# DAB_FM_Radio.net
KiCad netlist of a schematic drawn in EAGLE
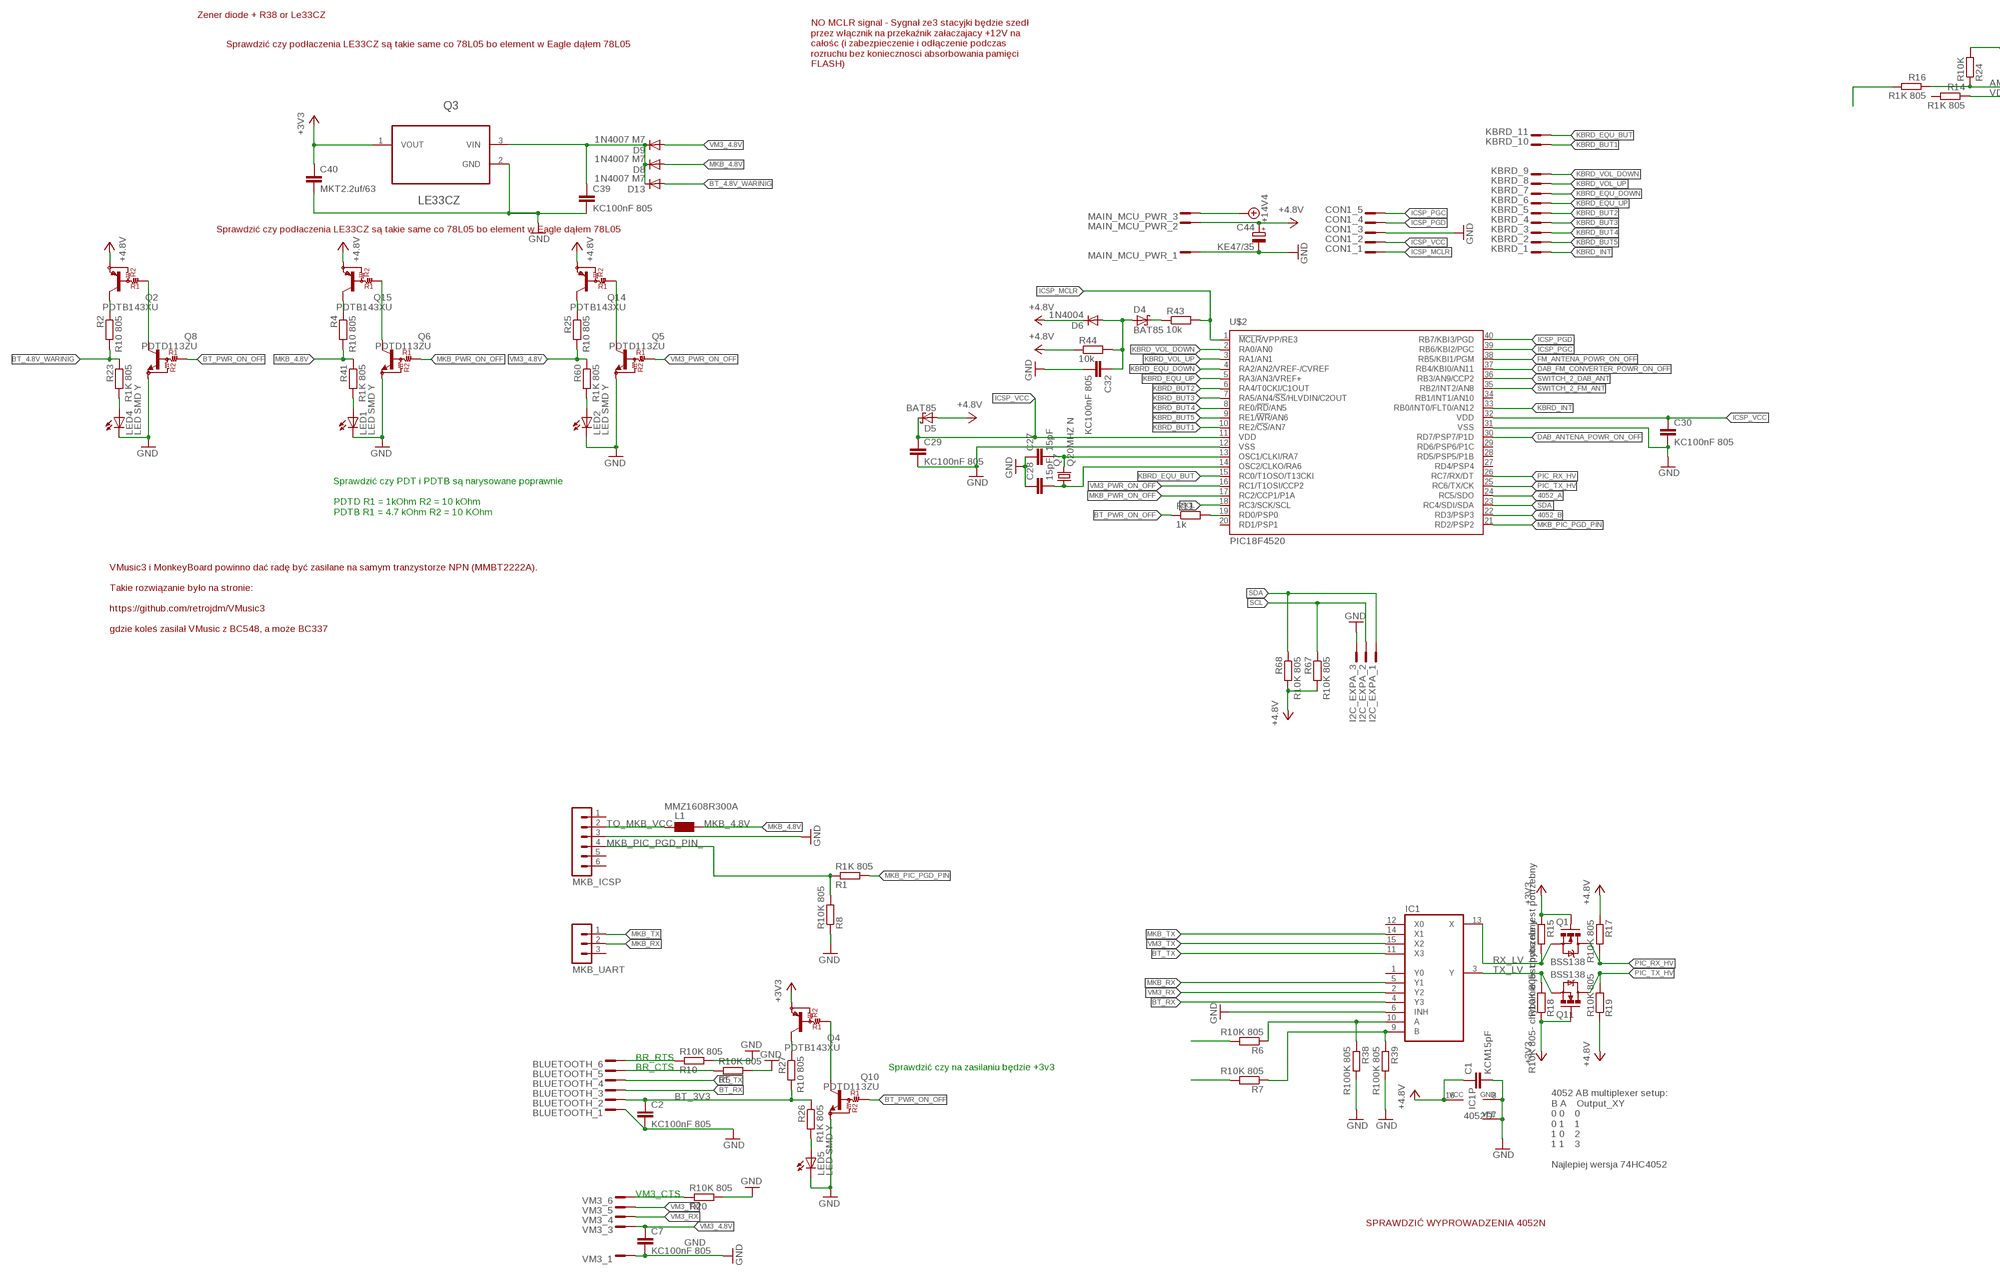
[diagram p0: schematic, sheet 1, part 1 of 2]
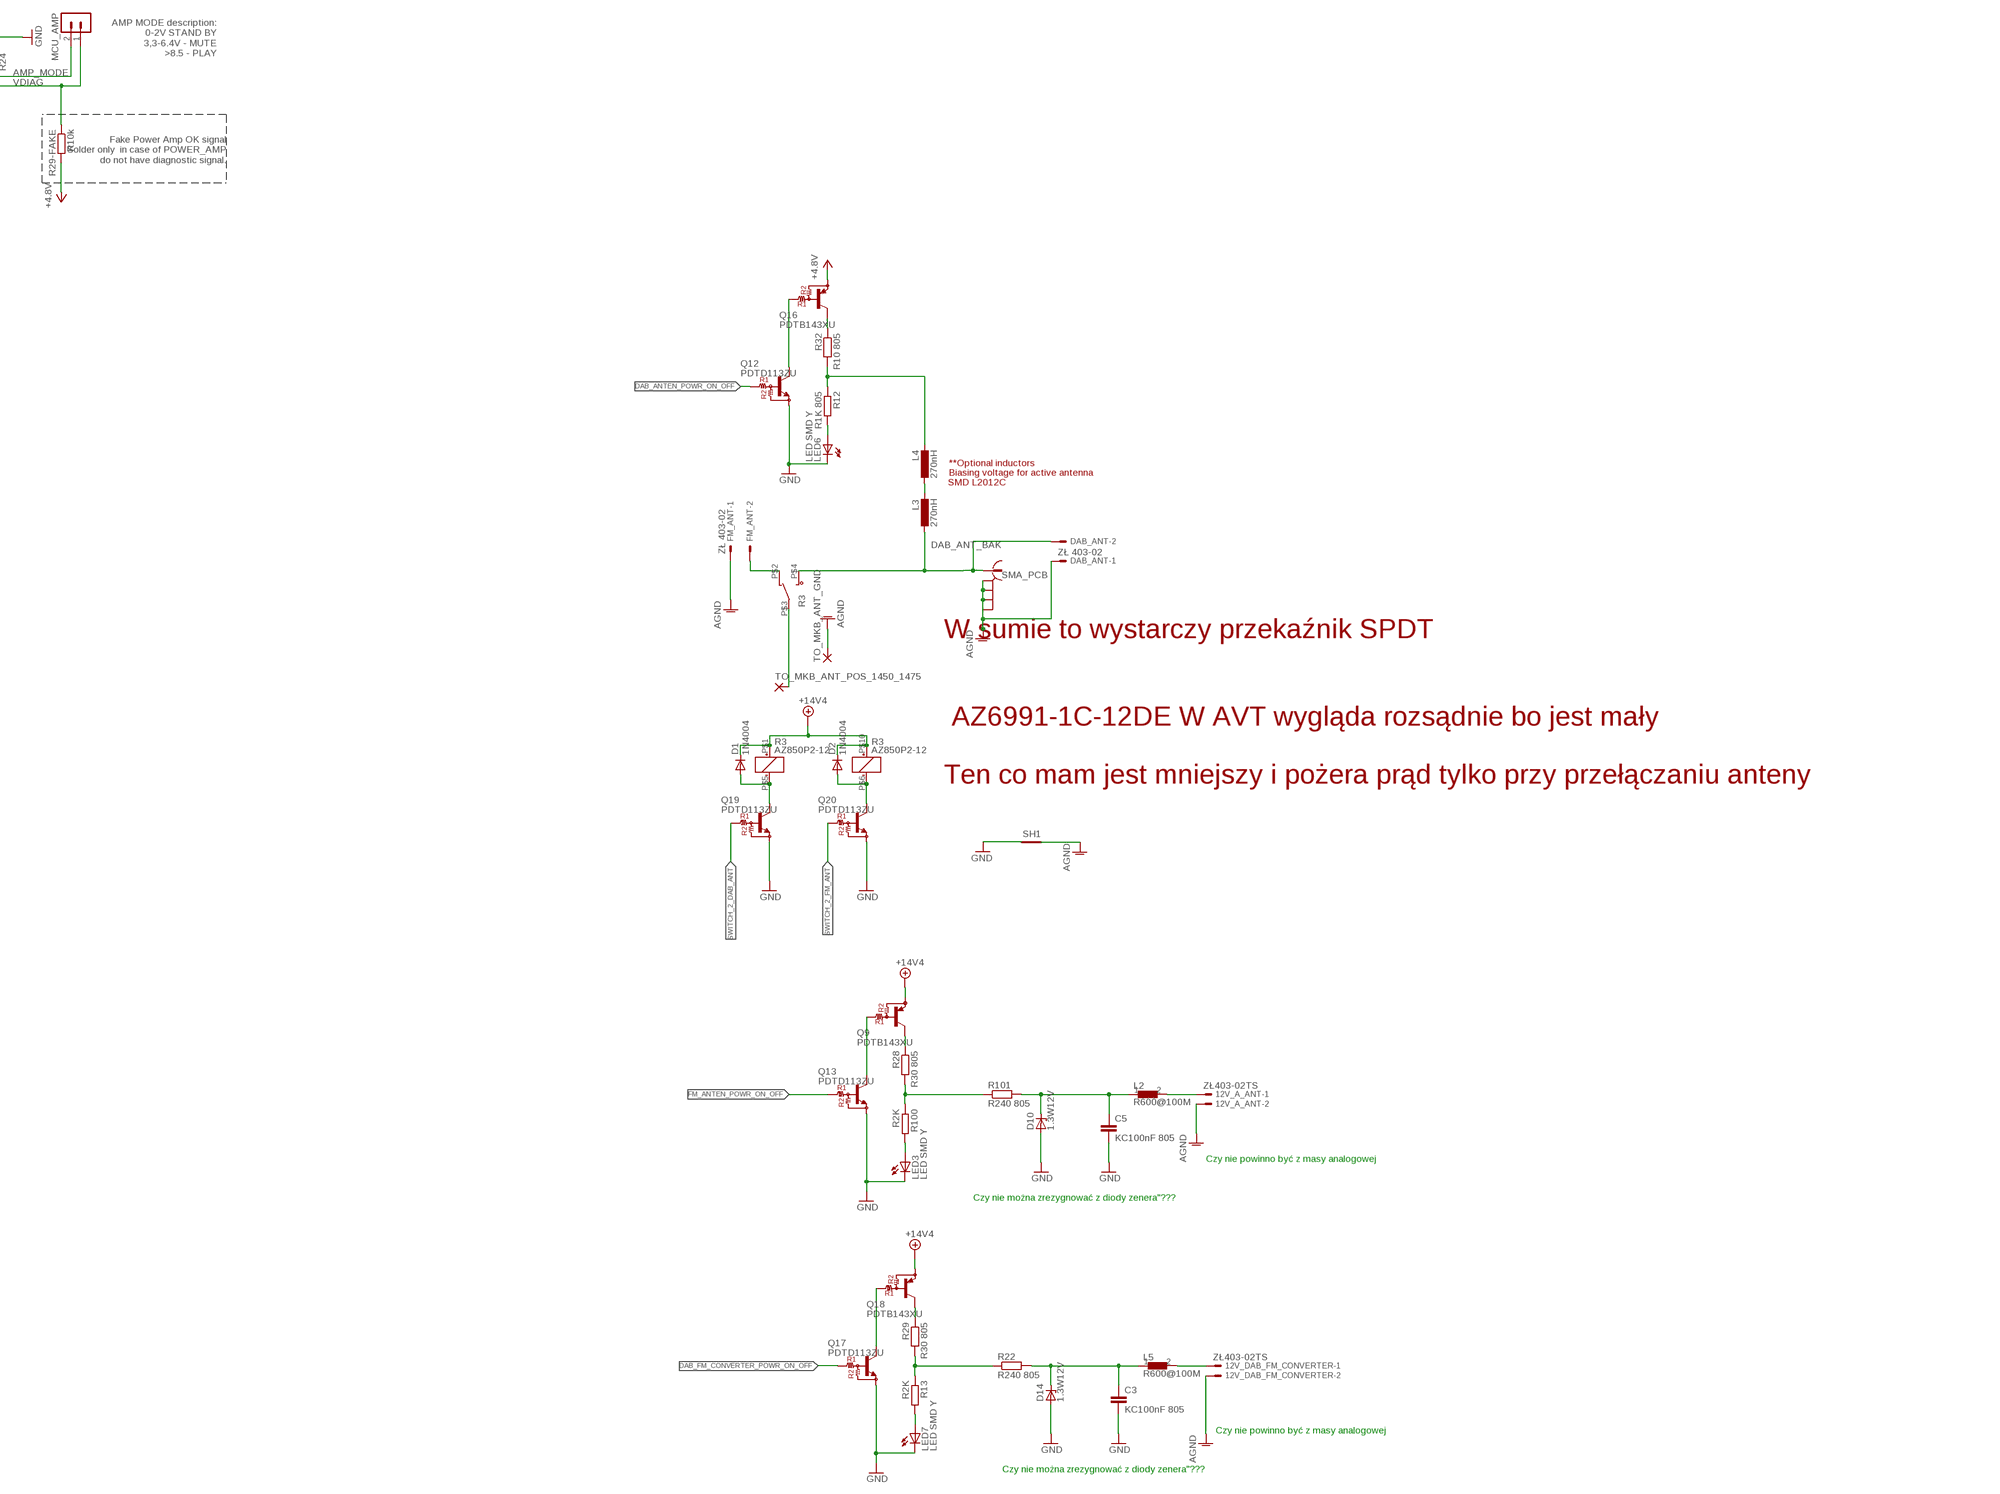
[diagram p1: schematic, sheet 1, part 2 of 2]

(export (version "E")
  (design (tool "Eeschema 10.0.6"))
  (components
    (comp (ref "12V_A_ANT")
      (value "ZŁ403-02TS")
      (footprint "eagle-import:22-23-2021")
      (fields (field (name "MF") "MOLEX") (field (name "MPN") "22-23-2021"))
      (libsource (lib "eagle-import") (part "22-23-2021"))
    )
    (comp (ref "12V_DAB_FM_CONVERTER")
      (value "ZŁ403-02TS")
      (footprint "eagle-import:22-23-2021")
      (fields (field (name "MF") "MOLEX") (field (name "MPN") "22-23-2021"))
      (libsource (lib "eagle-import") (part "22-23-2021"))
    )
    (comp (ref "BLUETOOTH")
      (value "JST_6_PIN_B6B-PH-KS")
      (footprint "eagle-import:B6B-PH-KS")
      (libsource (lib "eagle-import") (part "JST_6_PIN_B6B-PH-KS"))
    )
    (comp (ref "C1")
      (value "KCM15pF")
      (footprint "eagle-import:C0805")
      (libsource (lib "eagle-import") (part "C-EUC0805"))
    )
    (comp (ref "C2")
      (value "KC100nF 805")
      (footprint "eagle-import:C0805")
      (libsource (lib "eagle-import") (part "C-EUC0805"))
    )
    (comp (ref "C3")
      (value "KC100nF 805")
      (footprint "eagle-import:C0805")
      (libsource (lib "eagle-import") (part "C-EUC0805"))
    )
    (comp (ref "C5")
      (value "KC100nF 805")
      (footprint "eagle-import:C0805")
      (libsource (lib "eagle-import") (part "C-EUC0805"))
    )
    (comp (ref "C7")
      (value "KC100nF 805")
      (footprint "eagle-import:C0805")
      (libsource (lib "eagle-import") (part "C-EUC0805"))
    )
    (comp (ref "C27")
      (value "15pF")
      (footprint "eagle-import:C0805")
      (libsource (lib "eagle-import") (part "C-EUC0805"))
    )
    (comp (ref "C28")
      (value "15pF")
      (footprint "eagle-import:C0805")
      (libsource (lib "eagle-import") (part "C-EUC0805"))
    )
    (comp (ref "C29")
      (value "KC100nF 805")
      (footprint "eagle-import:C0805")
      (libsource (lib "eagle-import") (part "C-EUC0805"))
    )
    (comp (ref "C30")
      (value "KC100nF 805")
      (footprint "eagle-import:C0805")
      (libsource (lib "eagle-import") (part "C-EUC0805"))
    )
    (comp (ref "C32")
      (value "KC100nF 805")
      (footprint "eagle-import:C0805")
      (libsource (lib "eagle-import") (part "C-EUC0805"))
    )
    (comp (ref "C39")
      (value "KC100nF 805")
      (footprint "eagle-import:C0805")
      (libsource (lib "eagle-import") (part "C-EUC0805"))
    )
    (comp (ref "C40")
      (value "MKT2.2uf/63")
      (footprint "eagle-import:C025-030X050")
      (libsource (lib "eagle-import") (part "C-EU025-030X050"))
    )
    (comp (ref "C44")
      (value "KE47/35")
      (footprint "eagle-import:TT2D6")
      (libsource (lib "eagle-import") (part "CPOL-EUTT2D6"))
    )
    (comp (ref "CON1")
      (value "JST_5_PIN_B5B-PH-KS")
      (footprint "eagle-import:B5B-PH-KS")
      (libsource (lib "eagle-import") (part "JST_5_PIN_B5B-PH-KS"))
    )
    (comp (ref "D1")
      (value "1N4004")
      (footprint "eagle-import:DO41-7.6")
      (libsource (lib "eagle-import") (part "1N4004DO41-7.6"))
    )
    (comp (ref "D2")
      (value "1N4004")
      (footprint "eagle-import:DO41-7.6")
      (libsource (lib "eagle-import") (part "1N4004DO41-7.6"))
    )
    (comp (ref "D4")
      (value "BAT85")
      (footprint "eagle-import:DO34-V")
      (libsource (lib "eagle-import") (part "BAT85DO34-V"))
    )
    (comp (ref "D5")
      (value "BAT85")
      (footprint "eagle-import:DO34-5")
      (libsource (lib "eagle-import") (part "BAT85DO34-5"))
    )
    (comp (ref "D6")
      (value "1N4004")
      (footprint "eagle-import:DO41-V")
      (libsource (lib "eagle-import") (part "1N4004DO41-V"))
    )
    (comp (ref "D8")
      (value "1N4007 M7")
      (footprint "eagle-import:DO41-V")
      (libsource (lib "eagle-import") (part "1N4004DO41-V"))
    )
    (comp (ref "D9")
      (value "1N4007 M7")
      (footprint "eagle-import:DO41-V")
      (libsource (lib "eagle-import") (part "1N4004DO41-V"))
    )
    (comp (ref "D10")
      (value "1.3W12V")
      (footprint "eagle-import:ZDIO-2.5")
      (libsource (lib "eagle-import") (part "ZENER-DIODEZD-2.5"))
    )
    (comp (ref "D13")
      (value "1N4007 M7")
      (footprint "eagle-import:DO41-V")
      (libsource (lib "eagle-import") (part "1N4004DO41-V"))
    )
    (comp (ref "D14")
      (value "1.3W12V")
      (footprint "eagle-import:ZDIO-2.5")
      (libsource (lib "eagle-import") (part "ZENER-DIODEZD-2.5"))
    )
    (comp (ref "DAB_ANT")
      (value "ZŁ 403-02")
      (footprint "eagle-import:6410-02")
      (fields (field (name "OC_FARNELL") "unknown") (field (name "OC_NEWARK") "unknown"))
      (libsource (lib "eagle-import") (part "22-?-0227-2021"))
    )
    (comp (ref "DAB_ANT_BAK")
      (value "SMA_PCB")
      (footprint "eagle-import:SMA_PCB")
      (libsource (lib "eagle-import") (part "SMA_PCB"))
    )
    (comp (ref "FM_ANT")
      (value "ZŁ 403-02")
      (footprint "eagle-import:6410-02")
      (libsource (lib "eagle-import") (part "22-?-0227-2021"))
    )
    (comp (ref "I2C_EXPA")
      (value "JST_3_PIN_B3B-PH-KS")
      (footprint "eagle-import:B3B-PH-KS")
      (libsource (lib "eagle-import") (part "JST_3_PIN_B3B-PH-KS"))
    )
    (comp (ref "IC1")
      (value "4052D")
      (footprint "eagle-import:SO16")
      (libsource (lib "eagle-import") (part "4052D"))
    )
    (comp (ref "KBRD")
      (value "JST_11_PIN_B11B-PH-KS")
      (footprint "eagle-import:B11B-PH-KS")
      (libsource (lib "eagle-import") (part "JST_11_PIN_B11B-PH-KS"))
    )
    (comp (ref "L1")
      (value "MMZ1608R300A")
      (footprint "eagle-import:0603")
      (libsource (lib "eagle-import") (part "WE-CBF_0603"))
    )
    (comp (ref "L2")
      (value "R600@100M")
      (footprint "eagle-import:R0805")
      (libsource (lib "eagle-import") (part "FERRITR0805"))
    )
    (comp (ref "L3")
      (value "270nH")
      (footprint "eagle-import:L2012C")
      (libsource (lib "eagle-import") (part "L-EUL2012C"))
    )
    (comp (ref "L4")
      (value "270nH")
      (footprint "eagle-import:L2012C")
      (libsource (lib "eagle-import") (part "L-EUL2012C"))
    )
    (comp (ref "L5")
      (value "R600@100M")
      (footprint "eagle-import:R0805")
      (libsource (lib "eagle-import") (part "FERRITR0805"))
    )
    (comp (ref "LED1")
      (value "LED SMD Y")
      (footprint "eagle-import:CHIP-LED0805")
      (libsource (lib "eagle-import") (part "LEDCHIP-LED0805"))
    )
    (comp (ref "LED2")
      (value "LED SMD Y")
      (footprint "eagle-import:CHIP-LED0805")
      (libsource (lib "eagle-import") (part "LEDCHIP-LED0805"))
    )
    (comp (ref "LED3")
      (value "LED SMD Y")
      (footprint "eagle-import:SMARTLED-TTW")
      (libsource (lib "eagle-import") (part "LED"))
    )
    (comp (ref "LED4")
      (value "LED SMD Y")
      (footprint "eagle-import:CHIP-LED0805")
      (libsource (lib "eagle-import") (part "LEDCHIP-LED0805"))
    )
    (comp (ref "LED5")
      (value "LED SMD Y")
      (footprint "eagle-import:CHIP-LED0805")
      (libsource (lib "eagle-import") (part "LEDCHIP-LED0805"))
    )
    (comp (ref "LED6")
      (value "LED SMD Y")
      (footprint "eagle-import:SMARTLED-TTW")
      (libsource (lib "eagle-import") (part "LED"))
    )
    (comp (ref "LED7")
      (value "LED SMD Y")
      (footprint "eagle-import:SMARTLED-TTW")
      (libsource (lib "eagle-import") (part "LED"))
    )
    (comp (ref "MAIN_MCU_PWR")
      (value "JST_3_PIN_B3B-XH-A")
      (footprint "eagle-import:B3B-XH-A")
      (libsource (lib "eagle-import") (part "JST_3_PIN_B3B-XH-A"))
    )
    (comp (ref "MCU_AMP")
      (value "MA02-1")
      (footprint "eagle-import:MA02-1")
      (libsource (lib "eagle-import") (part "MA02-1"))
    )
    (comp (ref "MKB_ICSP")
      (value "MA06-1")
      (footprint "eagle-import:MA06-1")
      (libsource (lib "eagle-import") (part "MA06-1"))
    )
    (comp (ref "MKB_UART")
      (value "MA03-1")
      (footprint "eagle-import:MA03-1")
      (libsource (lib "eagle-import") (part "MA03-1"))
    )
    (comp (ref "Q1")
      (value "BSS138")
      (footprint "eagle-import:SOT23-3")
      (libsource (lib "eagle-import") (part "MOSFET-NCHANNELSMD"))
    )
    (comp (ref "Q2")
      (value "PDTB143XU")
      (footprint "eagle-import:SOT-23")
      (fields (field (name "R1") "4.7 kOhm") (field (name "R2") "10 kOhm"))
      (libsource (lib "eagle-import") (part "PDTB143XU"))
    )
    (comp (ref "Q3")
      (value "LE33CZ")
      (footprint "eagle-import:TO127P254X749-3")
      (libsource (lib "eagle-import") (part "LE33CZ"))
    )
    (comp (ref "Q4")
      (value "PDTB143XU")
      (footprint "eagle-import:SOT-23")
      (fields (field (name "R1") "4.7 kOhm") (field (name "R2") "10 kOhm"))
      (libsource (lib "eagle-import") (part "PDTB143XU"))
    )
    (comp (ref "Q5")
      (value "PDTD113ZU")
      (footprint "eagle-import:SOT-23")
      (libsource (lib "eagle-import") (part "PDTD113ZU"))
    )
    (comp (ref "Q6")
      (value "PDTD113ZU")
      (footprint "eagle-import:SOT-23")
      (fields (field (name "R1") "1 kOhm") (field (name "R2") "10 kOhm"))
      (libsource (lib "eagle-import") (part "PDTD113ZU"))
    )
    (comp (ref "Q7")
      (value "Q20MHZ N")
      (footprint "eagle-import:HC49_S")
      (libsource (lib "eagle-import") (part "CRYSTALHC49S"))
    )
    (comp (ref "Q8")
      (value "PDTD113ZU")
      (footprint "eagle-import:SOT-23")
      (fields (field (name "R1") "1 kOhm") (field (name "R2") "10 kOhm"))
      (libsource (lib "eagle-import") (part "PDTD113ZU"))
    )
    (comp (ref "Q9")
      (value "PDTB143XU")
      (footprint "eagle-import:SOT-23")
      (fields (field (name "R1") "4.7 kOhm") (field (name "R2") "10 kOhm"))
      (libsource (lib "eagle-import") (part "PDTB143XU"))
    )
    (comp (ref "Q10")
      (value "PDTD113ZU")
      (footprint "eagle-import:SOT-23")
      (fields (field (name "R1") "1 kOhm") (field (name "R2") "10 kOhm"))
      (libsource (lib "eagle-import") (part "PDTD113ZU"))
    )
    (comp (ref "Q11")
      (value "BSS138")
      (footprint "eagle-import:SOT23-3")
      (libsource (lib "eagle-import") (part "MOSFET-NCHANNELSMD"))
    )
    (comp (ref "Q12")
      (value "PDTD113ZU")
      (footprint "eagle-import:SOT-23")
      (fields (field (name "R1") "1 kOhm") (field (name "R2") "10 kOhm"))
      (libsource (lib "eagle-import") (part "PDTD113ZU"))
    )
    (comp (ref "Q13")
      (value "PDTD113ZU")
      (footprint "eagle-import:SOT-23")
      (fields (field (name "R1") "1 kOhm") (field (name "R2") "10 kOhm"))
      (libsource (lib "eagle-import") (part "PDTD113ZU"))
    )
    (comp (ref "Q14")
      (value "PDTB143XU")
      (footprint "eagle-import:SOT-23")
      (libsource (lib "eagle-import") (part "PDTB143XU"))
    )
    (comp (ref "Q15")
      (value "PDTB143XU")
      (footprint "eagle-import:SOT-23")
      (fields (field (name "R1") "4.7 kOhm") (field (name "R2") "10 kOhm"))
      (libsource (lib "eagle-import") (part "PDTB143XU"))
    )
    (comp (ref "Q16")
      (value "PDTB143XU")
      (footprint "eagle-import:SOT-23")
      (fields (field (name "R1") "4.7 kOhm") (field (name "R2") "10 kOhm"))
      (libsource (lib "eagle-import") (part "PDTB143XU"))
    )
    (comp (ref "Q17")
      (value "PDTD113ZU")
      (footprint "eagle-import:SOT-23")
      (fields (field (name "R1") "1 kOhm") (field (name "R2") "10 kOhm"))
      (libsource (lib "eagle-import") (part "PDTD113ZU"))
    )
    (comp (ref "Q18")
      (value "PDTB143XU")
      (footprint "eagle-import:SOT-23")
      (fields (field (name "R1") "4.7 kOhm") (field (name "R2") "10 kOhm"))
      (libsource (lib "eagle-import") (part "PDTB143XU"))
    )
    (comp (ref "Q19")
      (value "PDTD113ZU")
      (footprint "eagle-import:SOT-23")
      (fields (field (name "R1") "1 kOhm") (field (name "R2") "10 kOhm"))
      (libsource (lib "eagle-import") (part "PDTD113ZU"))
    )
    (comp (ref "Q20")
      (value "PDTD113ZU")
      (footprint "eagle-import:SOT-23")
      (fields (field (name "R1") "1 kOhm") (field (name "R2") "10 kOhm"))
      (libsource (lib "eagle-import") (part "PDTD113ZU"))
    )
    (comp (ref "R1")
      (value "R1K 805")
      (footprint "eagle-import:R0805")
      (libsource (lib "eagle-import") (part "R-EU_R0805"))
    )
    (comp (ref "R2")
      (value "R10 805")
      (footprint "eagle-import:R0805")
      (libsource (lib "eagle-import") (part "R-EU_R0805"))
    )
    (comp (ref "R3")
      (value "AZ850P2-12")
      (footprint "eagle-import:AZ850-2C")
      (libsource (lib "eagle-import") (part "AZ850P2-12"))
    )
    (comp (ref "R4")
      (value "R10 805")
      (footprint "eagle-import:R0805")
      (libsource (lib "eagle-import") (part "R-EU_R0805"))
    )
    (comp (ref "R5")
      (value "R10K 805")
      (footprint "eagle-import:R0805")
      (libsource (lib "eagle-import") (part "R-EU_R0805"))
    )
    (comp (ref "R6")
      (value "R10K 805")
      (footprint "eagle-import:R0805")
      (libsource (lib "eagle-import") (part "R-EU_R0805"))
    )
    (comp (ref "R7")
      (value "R10K 805")
      (footprint "eagle-import:R0805")
      (libsource (lib "eagle-import") (part "R-EU_R0805"))
    )
    (comp (ref "R8")
      (value "R10K 805")
      (footprint "eagle-import:R0805")
      (libsource (lib "eagle-import") (part "R-EU_R0805"))
    )
    (comp (ref "R10")
      (value "R10K 805")
      (footprint "eagle-import:R0805")
      (libsource (lib "eagle-import") (part "R-EU_R0805"))
    )
    (comp (ref "R11")
      (value "1k")
      (footprint "eagle-import:R0805")
      (libsource (lib "eagle-import") (part "R-EU_R0805"))
    )
    (comp (ref "R12")
      (value "R1K 805")
      (footprint "eagle-import:R0805")
      (libsource (lib "eagle-import") (part "R-EU_R0805"))
    )
    (comp (ref "R13")
      (value "R2K")
      (footprint "eagle-import:R0805")
      (libsource (lib "eagle-import") (part "R-EU_R0805"))
    )
    (comp (ref "R14")
      (value "R1K 805")
      (footprint "eagle-import:R0805")
      (libsource (lib "eagle-import") (part "R-EU_R0805"))
    )
    (comp (ref "R15")
      (value "R10K 805- chyba nie jest potrzebny")
      (footprint "eagle-import:R0805")
      (libsource (lib "eagle-import") (part "R-EU_R0805"))
    )
    (comp (ref "R16")
      (value "R1K 805")
      (footprint "eagle-import:R0805")
      (libsource (lib "eagle-import") (part "R-EU_R0805"))
    )
    (comp (ref "R17")
      (value "R10K 805")
      (footprint "eagle-import:R0805")
      (libsource (lib "eagle-import") (part "R-EU_R0805"))
    )
    (comp (ref "R18")
      (value "R10K 805- chyba nie jest potrzebny")
      (footprint "eagle-import:R0805")
      (libsource (lib "eagle-import") (part "R-EU_R0805"))
    )
    (comp (ref "R19")
      (value "R10K 805")
      (footprint "eagle-import:R0805")
      (libsource (lib "eagle-import") (part "R-EU_R0805"))
    )
    (comp (ref "R20")
      (value "R10K 805")
      (footprint "eagle-import:R0805")
      (libsource (lib "eagle-import") (part "R-EU_R0805"))
    )
    (comp (ref "R22")
      (value "R240 805")
      (footprint "eagle-import:M0805")
      (libsource (lib "eagle-import") (part "R-EU_M0805"))
    )
    (comp (ref "R23")
      (value "R1K 805")
      (footprint "eagle-import:R0805")
      (libsource (lib "eagle-import") (part "R-EU_R0805"))
    )
    (comp (ref "R24")
      (value "R10K")
      (footprint "eagle-import:R0805")
      (libsource (lib "eagle-import") (part "R-EU_R0805"))
    )
    (comp (ref "R25")
      (value "R10 805")
      (footprint "eagle-import:R0805")
      (libsource (lib "eagle-import") (part "R-EU_R0805"))
    )
    (comp (ref "R26")
      (value "R1K 805")
      (footprint "eagle-import:R0805")
      (libsource (lib "eagle-import") (part "R-EU_R0805"))
    )
    (comp (ref "R27")
      (value "R10 805")
      (footprint "eagle-import:R0805")
      (libsource (lib "eagle-import") (part "R-EU_R0805"))
    )
    (comp (ref "R28")
      (value "R30 805")
      (footprint "eagle-import:R0805")
      (libsource (lib "eagle-import") (part "R-EU_R0805"))
    )
    (comp (ref "R29")
      (value "R30 805")
      (footprint "eagle-import:R0805")
      (libsource (lib "eagle-import") (part "R-EU_R0805"))
    )
    (comp (ref "R29-FAKE")
      (value "R10k")
      (footprint "eagle-import:0204_7")
      (libsource (lib "eagle-import") (part "R-EU_0204/7"))
    )
    (comp (ref "R32")
      (value "R10 805")
      (footprint "eagle-import:R0805")
      (libsource (lib "eagle-import") (part "R-EU_R0805"))
    )
    (comp (ref "R38")
      (value "R100K 805")
      (footprint "eagle-import:M0805")
      (libsource (lib "eagle-import") (part "R-EU_M0805"))
    )
    (comp (ref "R39")
      (value "R100K 805")
      (footprint "eagle-import:M0805")
      (libsource (lib "eagle-import") (part "R-EU_M0805"))
    )
    (comp (ref "R41")
      (value "R1K 805")
      (footprint "eagle-import:R0805")
      (libsource (lib "eagle-import") (part "R-EU_R0805"))
    )
    (comp (ref "R43")
      (value "10k")
      (footprint "eagle-import:R0805")
      (libsource (lib "eagle-import") (part "R-EU_R0805"))
    )
    (comp (ref "R44")
      (value "10k")
      (footprint "eagle-import:M0805")
      (libsource (lib "eagle-import") (part "R-EU_M0805"))
    )
    (comp (ref "R60")
      (value "R1K 805")
      (footprint "eagle-import:R0805")
      (libsource (lib "eagle-import") (part "R-EU_R0805"))
    )
    (comp (ref "R67")
      (value "R10K 805")
      (footprint "eagle-import:R0805")
      (libsource (lib "eagle-import") (part "R-EU_R0805"))
    )
    (comp (ref "R68")
      (value "R10K 805")
      (footprint "eagle-import:R0805")
      (libsource (lib "eagle-import") (part "R-EU_R0805"))
    )
    (comp (ref "R100")
      (value "R2K")
      (footprint "eagle-import:R0805")
      (libsource (lib "eagle-import") (part "R-EU_R0805"))
    )
    (comp (ref "R101")
      (value "R240 805")
      (footprint "eagle-import:M0805")
      (libsource (lib "eagle-import") (part "R-EU_M0805"))
    )
    (comp (ref "SH1")
      (value "SHORT-HT5")
      (footprint "eagle-import:SHORT_TOP-50")
      (libsource (lib "eagle-import") (part "SHORT-HT5"))
    )
    (comp (ref "TO_MKB_ANT_GND")
      (value "2,54/0,8")
      (footprint "eagle-import:2,54_0,8")
      (libsource (lib "eagle-import") (part "2,54/0,8"))
    )
    (comp (ref "TO_MKB_ANT_POS_1450_1475")
      (value "2,54/0,8")
      (footprint "eagle-import:2,54_0,8")
      (libsource (lib "eagle-import") (part "2,54/0,8"))
    )
    (comp (ref "U$2")
      (value "PIC18F4520")
      (footprint "eagle-import:DIL40")
      (libsource (lib "eagle-import") (part "PIC18F4205"))
    )
    (comp (ref "VM3")
      (value "JST_6_PIN_B6B-PH-KS")
      (footprint "eagle-import:B6B-PH-KS")
      (libsource (lib "eagle-import") (part "JST_6_PIN_B6B-PH-KS"))
    )
  )
  (nets
    (net (code "1") (name "+3V3") (class "Default")
      (node (ref "C40") (pin "1") (pinfunction "1_1") (pintype "passive"))
      (node (ref "Q1") (pin "1") (pinfunction "G_1") (pintype "passive"))
      (node (ref "Q11") (pin "1") (pinfunction "G_1") (pintype "passive"))
      (node (ref "Q3") (pin "1") (pinfunction "VOUT_1") (pintype "output"))
      (node (ref "Q4") (pin "2") (pinfunction "E_2") (pintype "passive"))
      (node (ref "R15") (pin "1") (pinfunction "1_1") (pintype "passive"))
      (node (ref "R18") (pin "1") (pinfunction "1_1") (pintype "passive"))
    )
    (net (code "2") (name "+4.8V") (class "Default")
      (node (ref "C1") (pin "1") (pinfunction "1_1") (pintype "passive"))
      (node (ref "C44") (pin "+") (pinfunction "+_+") (pintype "passive"))
      (node (ref "D5") (pin "A") (pinfunction "A_A") (pintype "passive"))
      (node (ref "D6") (pin "C") (pinfunction "C_C") (pintype "passive"))
      (node (ref "IC1") (pin "16") (pinfunction "VCC_16") (pintype "power_in"))
      (node (ref "MAIN_MCU_PWR") (pin "P$2") (pinfunction "P$1_P$2") (pintype "bidirectional"))
      (node (ref "Q14") (pin "2") (pinfunction "E_2") (pintype "passive"))
      (node (ref "Q15") (pin "2") (pinfunction "E_2") (pintype "passive"))
      (node (ref "Q16") (pin "2") (pinfunction "E_2") (pintype "passive"))
      (node (ref "Q2") (pin "2") (pinfunction "E_2") (pintype "passive"))
      (node (ref "R17") (pin "1") (pinfunction "1_1") (pintype "passive"))
      (node (ref "R19") (pin "1") (pinfunction "1_1") (pintype "passive"))
      (node (ref "R29-FAKE") (pin "2") (pinfunction "2_2") (pintype "passive"))
      (node (ref "R44") (pin "1") (pinfunction "1_1") (pintype "passive"))
      (node (ref "R67") (pin "2") (pinfunction "2_2") (pintype "passive"))
      (node (ref "R68") (pin "2") (pinfunction "2_2") (pintype "passive"))
    )
    (net (code "3") (name "+14V4") (class "Default")
      (node (ref "D1") (pin "C") (pinfunction "C_C") (pintype "passive"))
      (node (ref "D2") (pin "C") (pinfunction "C_C") (pintype "passive"))
      (node (ref "MAIN_MCU_PWR") (pin "P$3") (pinfunction "P$1_P$3") (pintype "bidirectional"))
      (node (ref "Q18") (pin "2") (pinfunction "E_2") (pintype "passive"))
      (node (ref "Q9") (pin "2") (pinfunction "E_2") (pintype "passive"))
      (node (ref "R3") (pin "P$1") (pinfunction "+_P$1") (pintype "passive"))
      (node (ref "R3") (pin "P$10") (pinfunction "+_P$10") (pintype "passive"))
    )
    (net (code "4") (name "/AMP_MODE") (class "Default")
      (node (ref "MCU_AMP") (pin "2") (pinfunction "2_2") (pintype "passive"))
      (node (ref "R16") (pin "1") (pinfunction "1_1") (pintype "passive"))
      (node (ref "R24") (pin "1") (pinfunction "1_1") (pintype "passive"))
    )
    (net (code "5") (name "/BT_3V3") (class "Default")
      (node (ref "BLUETOOTH") (pin "P$2") (pinfunction "P$1_P$2") (pintype "bidirectional"))
      (node (ref "C2") (pin "1") (pinfunction "1_1") (pintype "passive"))
      (node (ref "R26") (pin "1") (pinfunction "1_1") (pintype "passive"))
      (node (ref "R27") (pin "2") (pinfunction "2_2") (pintype "passive"))
    )
    (net (code "6") (name "/MKB_PIC_PGD_PIN_") (class "Default")
      (node (ref "MKB_ICSP") (pin "4") (pinfunction "4_4") (pintype "passive"))
      (node (ref "R1") (pin "1") (pinfunction "1_1") (pintype "passive"))
      (node (ref "R8") (pin "2") (pinfunction "2_2") (pintype "passive"))
    )
    (net (code "7") (name "/RX_LV") (class "Default")
      (node (ref "IC1") (pin "13") (pinfunction "X_13") (pintype "bidirectional"))
      (node (ref "Q1") (pin "2") (pinfunction "S_2") (pintype "passive"))
      (node (ref "R15") (pin "2") (pinfunction "2_2") (pintype "passive"))
    )
    (net (code "8") (name "/TO_MKB_VCC") (class "Default")
      (node (ref "L1") (pin "1") (pinfunction "1_1") (pintype "passive"))
      (node (ref "MKB_ICSP") (pin "2") (pinfunction "2_2") (pintype "passive"))
    )
    (net (code "9") (name "/TX_LV") (class "Default")
      (node (ref "IC1") (pin "3") (pinfunction "Y_3") (pintype "bidirectional"))
      (node (ref "Q11") (pin "2") (pinfunction "S_2") (pintype "passive"))
      (node (ref "R18") (pin "2") (pinfunction "2_2") (pintype "passive"))
    )
    (net (code "10") (name "/VDIAG") (class "Default")
      (node (ref "MCU_AMP") (pin "1") (pinfunction "1_1") (pintype "passive"))
      (node (ref "R14") (pin "1") (pinfunction "1_1") (pintype "passive"))
      (node (ref "R29-FAKE") (pin "1") (pinfunction "1_1") (pintype "passive"))
    )
    (net (code "11") (name "4052_A") (class "Default")
      (node (ref "R6") (pin "2") (pinfunction "2_2") (pintype "passive"))
      (node (ref "U$2") (pin "24") (pinfunction "RC5/SDO_24") (pintype "bidirectional"))
    )
    (net (code "12") (name "4052_B") (class "Default")
      (node (ref "R7") (pin "2") (pinfunction "2_2") (pintype "passive"))
      (node (ref "U$2") (pin "22") (pinfunction "RD3/PSP3_22") (pintype "bidirectional"))
    )
    (net (code "13") (name "AGND") (class "Default")
      (node (ref "12V_A_ANT") (pin "2") (pinfunction "S_2") (pintype "passive"))
      (node (ref "12V_DAB_FM_CONVERTER") (pin "2") (pinfunction "S_2") (pintype "passive"))
      (node (ref "DAB_ANT") (pin "1") (pinfunction "S_1") (pintype "passive"))
      (node (ref "DAB_ANT_BAK") (pin "GND@1") (pinfunction "GND_GND@1") (pintype "power_in"))
      (node (ref "DAB_ANT_BAK") (pin "GND@2") (pinfunction "GND_GND@2") (pintype "power_in"))
      (node (ref "DAB_ANT_BAK") (pin "GND@3") (pinfunction "GND_GND@3") (pintype "power_in"))
      (node (ref "DAB_ANT_BAK") (pin "GND@4") (pinfunction "GND_GND@4") (pintype "power_in"))
      (node (ref "FM_ANT") (pin "1") (pinfunction "S_1") (pintype "passive"))
      (node (ref "SH1") (pin "2") (pinfunction "P$2_2") (pintype "bidirectional"))
      (node (ref "TO_MKB_ANT_GND") (pin "1") (pinfunction "P_1") (pintype "passive"))
    )
    (net (code "14") (name "BT_4.8V_WARINIG") (class "Default")
      (node (ref "D13") (pin "A") (pinfunction "A_A") (pintype "passive"))
      (node (ref "R2") (pin "2") (pinfunction "2_2") (pintype "passive"))
      (node (ref "R23") (pin "1") (pinfunction "1_1") (pintype "passive"))
    )
    (net (code "15") (name "BT_PWR_ON_OFF") (class "Default")
      (node (ref "Q10") (pin "1") (pinfunction "B_1") (pintype "passive"))
      (node (ref "Q8") (pin "1") (pinfunction "B_1") (pintype "passive"))
      (node (ref "R11") (pin "1") (pinfunction "1_1") (pintype "passive"))
    )
    (net (code "16") (name "BT_RX") (class "Default")
      (node (ref "BLUETOOTH") (pin "P$3") (pinfunction "P$1_P$3") (pintype "bidirectional"))
      (node (ref "IC1") (pin "4") (pinfunction "Y3_4") (pintype "bidirectional"))
    )
    (net (code "17") (name "BT_TX") (class "Default")
      (node (ref "BLUETOOTH") (pin "P$4") (pinfunction "P$1_P$4") (pintype "bidirectional"))
      (node (ref "IC1") (pin "11") (pinfunction "X3_11") (pintype "bidirectional"))
    )
    (net (code "18") (name "DAB_ANTENA_POWR_ON_OFF") (class "Default")
      (node (ref "U$2") (pin "30") (pinfunction "RD7/PSP7/P1D_30") (pintype "bidirectional"))
    )
    (net (code "19") (name "DAB_ANTEN_POWR_ON_OFF") (class "Default")
      (node (ref "Q12") (pin "1") (pinfunction "B_1") (pintype "passive"))
    )
    (net (code "20") (name "DAB_FM_CONVERTER_POWR_ON_OFF") (class "Default")
      (node (ref "Q17") (pin "1") (pinfunction "B_1") (pintype "passive"))
      (node (ref "U$2") (pin "37") (pinfunction "RB4/KBI0/AN11_37") (pintype "bidirectional"))
    )
    (net (code "21") (name "FM_ANTENA_POWR_ON_OFF") (class "Default")
      (node (ref "U$2") (pin "38") (pinfunction "RB5/KBI1/PGM_38") (pintype "bidirectional"))
    )
    (net (code "22") (name "FM_ANTEN_POWR_ON_OFF") (class "Default")
      (node (ref "Q13") (pin "1") (pinfunction "B_1") (pintype "passive"))
    )
    (net (code "23") (name "GND") (class "Default")
      (node (ref "BLUETOOTH") (pin "P$1") (pinfunction "P$1_P$1") (pintype "bidirectional"))
      (node (ref "C1") (pin "2") (pinfunction "2_2") (pintype "passive"))
      (node (ref "C2") (pin "2") (pinfunction "2_2") (pintype "passive"))
      (node (ref "C27") (pin "1") (pinfunction "1_1") (pintype "passive"))
      (node (ref "C28") (pin "1") (pinfunction "1_1") (pintype "passive"))
      (node (ref "C29") (pin "2") (pinfunction "2_2") (pintype "passive"))
      (node (ref "C3") (pin "2") (pinfunction "2_2") (pintype "passive"))
      (node (ref "C30") (pin "2") (pinfunction "2_2") (pintype "passive"))
      (node (ref "C32") (pin "2") (pinfunction "2_2") (pintype "passive"))
      (node (ref "C39") (pin "2") (pinfunction "2_2") (pintype "passive"))
      (node (ref "C40") (pin "2") (pinfunction "2_2") (pintype "passive"))
      (node (ref "C44") (pin "-") (pinfunction "-_-") (pintype "passive"))
      (node (ref "C5") (pin "2") (pinfunction "2_2") (pintype "passive"))
      (node (ref "C7") (pin "2") (pinfunction "2_2") (pintype "passive"))
      (node (ref "CON1") (pin "P$3") (pinfunction "P$1_P$3") (pintype "bidirectional"))
      (node (ref "D10") (pin "A") (pinfunction "A_A") (pintype "passive"))
      (node (ref "D14") (pin "A") (pinfunction "A_A") (pintype "passive"))
      (node (ref "I2C_EXPA") (pin "P$3") (pinfunction "P$1_P$3") (pintype "bidirectional"))
      (node (ref "IC1") (pin "6") (pinfunction "INH_6") (pintype "input"))
      (node (ref "IC1") (pin "7") (pinfunction "VEE_7") (pintype "power_in"))
      (node (ref "IC1") (pin "8") (pinfunction "GND_8") (pintype "power_in"))
      (node (ref "LED1") (pin "C") (pinfunction "C_C") (pintype "passive"))
      (node (ref "LED2") (pin "C") (pinfunction "C_C") (pintype "passive"))
      (node (ref "LED3") (pin "C@1") (pinfunction "C_C@1") (pintype "passive"))
      (node (ref "LED4") (pin "C") (pinfunction "C_C") (pintype "passive"))
      (node (ref "LED5") (pin "C") (pinfunction "C_C") (pintype "passive"))
      (node (ref "LED6") (pin "C@1") (pinfunction "C_C@1") (pintype "passive"))
      (node (ref "LED7") (pin "C@1") (pinfunction "C_C@1") (pintype "passive"))
      (node (ref "MAIN_MCU_PWR") (pin "P$1") (pinfunction "P$1_P$1") (pintype "bidirectional"))
      (node (ref "MKB_ICSP") (pin "3") (pinfunction "3_3") (pintype "passive"))
      (node (ref "Q10") (pin "2") (pinfunction "E_2") (pintype "passive"))
      (node (ref "Q12") (pin "2") (pinfunction "E_2") (pintype "passive"))
      (node (ref "Q13") (pin "2") (pinfunction "E_2") (pintype "passive"))
      (node (ref "Q17") (pin "2") (pinfunction "E_2") (pintype "passive"))
      (node (ref "Q19") (pin "2") (pinfunction "E_2") (pintype "passive"))
      (node (ref "Q20") (pin "2") (pinfunction "E_2") (pintype "passive"))
      (node (ref "Q3") (pin "2") (pinfunction "GND_2") (pintype "passive"))
      (node (ref "Q5") (pin "2") (pinfunction "E_2") (pintype "passive"))
      (node (ref "Q6") (pin "2") (pinfunction "E_2") (pintype "passive"))
      (node (ref "Q8") (pin "2") (pinfunction "E_2") (pintype "passive"))
      (node (ref "R10") (pin "2") (pinfunction "2_2") (pintype "passive"))
      (node (ref "R20") (pin "2") (pinfunction "2_2") (pintype "passive"))
      (node (ref "R24") (pin "2") (pinfunction "2_2") (pintype "passive"))
      (node (ref "R38") (pin "2") (pinfunction "2_2") (pintype "passive"))
      (node (ref "R39") (pin "2") (pinfunction "2_2") (pintype "passive"))
      (node (ref "R5") (pin "2") (pinfunction "2_2") (pintype "passive"))
      (node (ref "R8") (pin "1") (pinfunction "1_1") (pintype "passive"))
      (node (ref "SH1") (pin "1") (pinfunction "P$1_1") (pintype "bidirectional"))
      (node (ref "U$2") (pin "12") (pinfunction "VSS_12") (pintype "power_in"))
      (node (ref "U$2") (pin "31") (pinfunction "VSS_31") (pintype "power_in"))
      (node (ref "VM3") (pin "P$1") (pinfunction "P$1_P$1") (pintype "bidirectional"))
    )
    (net (code "24") (name "ICSP_MCLR") (class "Default")
      (node (ref "CON1") (pin "P$1") (pinfunction "P$1_P$1") (pintype "bidirectional"))
      (node (ref "R43") (pin "2") (pinfunction "2_2") (pintype "passive"))
      (node (ref "U$2") (pin "1") (pinfunction "~{MCLR}/VPP/RE3_1") (pintype "input"))
    )
    (net (code "25") (name "ICSP_PGC") (class "Default")
      (node (ref "CON1") (pin "P$5") (pinfunction "P$1_P$5") (pintype "bidirectional"))
      (node (ref "U$2") (pin "39") (pinfunction "RB6/KBI2/PGC_39") (pintype "bidirectional"))
    )
    (net (code "26") (name "ICSP_PGD") (class "Default")
      (node (ref "CON1") (pin "P$4") (pinfunction "P$1_P$4") (pintype "bidirectional"))
      (node (ref "U$2") (pin "40") (pinfunction "RB7/KBI3/PGD_40") (pintype "bidirectional"))
    )
    (net (code "27") (name "ICSP_VCC") (class "Default")
      (node (ref "C29") (pin "1") (pinfunction "1_1") (pintype "passive"))
      (node (ref "C30") (pin "1") (pinfunction "1_1") (pintype "passive"))
      (node (ref "CON1") (pin "P$2") (pinfunction "P$1_P$2") (pintype "bidirectional"))
      (node (ref "D5") (pin "C") (pinfunction "C_C") (pintype "passive"))
      (node (ref "U$2") (pin "11") (pinfunction "VDD_11") (pintype "power_in"))
      (node (ref "U$2") (pin "32") (pinfunction "VDD_32") (pintype "power_in"))
    )
    (net (code "28") (name "KBRD_BUT1") (class "Default")
      (node (ref "KBRD") (pin "P$10") (pinfunction "P$1_P$10") (pintype "bidirectional"))
      (node (ref "U$2") (pin "10") (pinfunction "RE2/~{CS}/AN7_10") (pintype "bidirectional"))
    )
    (net (code "29") (name "KBRD_BUT2") (class "Default")
      (node (ref "KBRD") (pin "P$5") (pinfunction "P$1_P$5") (pintype "bidirectional"))
      (node (ref "U$2") (pin "6") (pinfunction "RA4/T0CKI/C1OUT_6") (pintype "bidirectional"))
    )
    (net (code "30") (name "KBRD_BUT3") (class "Default")
      (node (ref "KBRD") (pin "P$4") (pinfunction "P$1_P$4") (pintype "bidirectional"))
      (node (ref "U$2") (pin "7") (pinfunction "RA5/AN4/~{SS}/HLVDIN/C2OUT_7") (pintype "bidirectional"))
    )
    (net (code "31") (name "KBRD_BUT4") (class "Default")
      (node (ref "KBRD") (pin "P$3") (pinfunction "P$1_P$3") (pintype "bidirectional"))
      (node (ref "U$2") (pin "8") (pinfunction "RE0/~{RD}/AN5_8") (pintype "bidirectional"))
    )
    (net (code "32") (name "KBRD_BUT5") (class "Default")
      (node (ref "KBRD") (pin "P$2") (pinfunction "P$1_P$2") (pintype "bidirectional"))
      (node (ref "U$2") (pin "9") (pinfunction "RE1/~{WR}/AN6_9") (pintype "bidirectional"))
    )
    (net (code "33") (name "KBRD_EQU_BUT") (class "Default")
      (node (ref "KBRD") (pin "P$11") (pinfunction "P$1_P$11") (pintype "bidirectional"))
      (node (ref "U$2") (pin "15") (pinfunction "RC0/T1OSO/T13CKI_15") (pintype "bidirectional"))
    )
    (net (code "34") (name "KBRD_EQU_DOWN") (class "Default")
      (node (ref "KBRD") (pin "P$7") (pinfunction "P$1_P$7") (pintype "bidirectional"))
      (node (ref "U$2") (pin "4") (pinfunction "RA2/AN2/VREF-/CVREF_4") (pintype "bidirectional"))
    )
    (net (code "35") (name "KBRD_EQU_UP") (class "Default")
      (node (ref "KBRD") (pin "P$6") (pinfunction "P$1_P$6") (pintype "bidirectional"))
      (node (ref "U$2") (pin "5") (pinfunction "RA3/AN3/VREF+_5") (pintype "bidirectional"))
    )
    (net (code "36") (name "KBRD_INT") (class "Default")
      (node (ref "KBRD") (pin "P$1") (pinfunction "P$1_P$1") (pintype "bidirectional"))
      (node (ref "U$2") (pin "33") (pinfunction "RB0/INT0/FLT0/AN12_33") (pintype "bidirectional"))
    )
    (net (code "37") (name "KBRD_VOL_DOWN") (class "Default")
      (node (ref "KBRD") (pin "P$9") (pinfunction "P$1_P$9") (pintype "bidirectional"))
      (node (ref "U$2") (pin "2") (pinfunction "RA0/AN0_2") (pintype "bidirectional"))
    )
    (net (code "38") (name "KBRD_VOL_UP") (class "Default")
      (node (ref "KBRD") (pin "P$8") (pinfunction "P$1_P$8") (pintype "bidirectional"))
      (node (ref "U$2") (pin "3") (pinfunction "RA1/AN1_3") (pintype "bidirectional"))
    )
    (net (code "39") (name "MKB_4.8V") (class "Default")
      (node (ref "D8") (pin "A") (pinfunction "A_A") (pintype "passive"))
      (node (ref "L1") (pin "2") (pinfunction "2_2") (pintype "passive"))
      (node (ref "R4") (pin "2") (pinfunction "2_2") (pintype "passive"))
      (node (ref "R41") (pin "1") (pinfunction "1_1") (pintype "passive"))
    )
    (net (code "40") (name "MKB_PIC_PGD_PIN") (class "Default")
      (node (ref "R1") (pin "2") (pinfunction "2_2") (pintype "passive"))
      (node (ref "U$2") (pin "21") (pinfunction "RD2/PSP2_21") (pintype "bidirectional"))
    )
    (net (code "41") (name "MKB_PWR_ON_OFF") (class "Default")
      (node (ref "Q6") (pin "1") (pinfunction "B_1") (pintype "passive"))
      (node (ref "U$2") (pin "17") (pinfunction "RC2/CCP1/P1A_17") (pintype "bidirectional"))
    )
    (net (code "42") (name "MKB_RX") (class "Default")
      (node (ref "IC1") (pin "5") (pinfunction "Y1_5") (pintype "bidirectional"))
      (node (ref "MKB_UART") (pin "2") (pinfunction "2_2") (pintype "passive"))
    )
    (net (code "43") (name "MKB_TX") (class "Default")
      (node (ref "IC1") (pin "14") (pinfunction "X1_14") (pintype "bidirectional"))
      (node (ref "MKB_UART") (pin "1") (pinfunction "1_1") (pintype "passive"))
    )
    (net (code "44") (name "Net-(12V_A_ANTA-S)") (class "Default")
      (node (ref "12V_A_ANT") (pin "1") (pinfunction "S_1") (pintype "passive"))
      (node (ref "L2") (pin "2") (pinfunction "2_2") (pintype "passive"))
    )
    (net (code "45") (name "Net-(12V_DAB_FM_CONVERTERA-S)") (class "Default")
      (node (ref "12V_DAB_FM_CONVERTER") (pin "1") (pinfunction "S_1") (pintype "passive"))
      (node (ref "L5") (pin "2") (pinfunction "2_2") (pintype "passive"))
    )
    (net (code "46") (name "Net-(BLUETOOTHE-P$1)") (class "Default")
      (node (ref "BLUETOOTH") (pin "P$5") (pinfunction "P$1_P$5") (pintype "bidirectional"))
      (node (ref "R5") (pin "1") (pinfunction "1_1") (pintype "passive"))
    )
    (net (code "47") (name "Net-(BLUETOOTHF-P$1)") (class "Default")
      (node (ref "BLUETOOTH") (pin "P$6") (pinfunction "P$1_P$6") (pintype "bidirectional"))
      (node (ref "R10") (pin "1") (pinfunction "1_1") (pintype "passive"))
    )
    (net (code "48") (name "Net-(C3-Pad1)") (class "Default")
      (node (ref "C3") (pin "1") (pinfunction "1_1") (pintype "passive"))
      (node (ref "D14") (pin "C") (pinfunction "C_C") (pintype "passive"))
      (node (ref "L5") (pin "1") (pinfunction "1_1") (pintype "passive"))
      (node (ref "R22") (pin "2") (pinfunction "2_2") (pintype "passive"))
    )
    (net (code "49") (name "Net-(C5-Pad1)") (class "Default")
      (node (ref "C5") (pin "1") (pinfunction "1_1") (pintype "passive"))
      (node (ref "D10") (pin "C") (pinfunction "C_C") (pintype "passive"))
      (node (ref "L2") (pin "1") (pinfunction "1_1") (pintype "passive"))
      (node (ref "R101") (pin "2") (pinfunction "2_2") (pintype "passive"))
    )
    (net (code "50") (name "Net-(C32-Pad1)") (class "Default")
      (node (ref "C32") (pin "1") (pinfunction "1_1") (pintype "passive"))
      (node (ref "D4") (pin "A") (pinfunction "A_A") (pintype "passive"))
      (node (ref "D6") (pin "A") (pinfunction "A_A") (pintype "passive"))
      (node (ref "R44") (pin "2") (pinfunction "2_2") (pintype "passive"))
    )
    (net (code "51") (name "Net-(D4-PadC)") (class "Default")
      (node (ref "D4") (pin "C") (pinfunction "C_C") (pintype "passive"))
      (node (ref "R43") (pin "1") (pinfunction "1_1") (pintype "passive"))
    )
    (net (code "52") (name "Net-(DAB_ANTB-S)") (class "Default")
      (node (ref "DAB_ANT") (pin "2") (pinfunction "S_2") (pintype "passive"))
      (node (ref "DAB_ANT_BAK") (pin "P$1") (pinfunction "1_P$1") (pintype "passive"))
      (node (ref "L3") (pin "2") (pinfunction "2_2") (pintype "passive"))
      (node (ref "R3") (pin "P$4") (pinfunction "6_P$4") (pintype "passive"))
    )
    (net (code "53") (name "Net-(FM_ANTB-S)") (class "Default")
      (node (ref "FM_ANT") (pin "2") (pinfunction "S_2") (pintype "passive"))
      (node (ref "R3") (pin "P$2") (pinfunction "4_P$2") (pintype "passive"))
    )
    (net (code "54") (name "Net-(IC1A-A)") (class "Default")
      (node (ref "IC1") (pin "10") (pinfunction "A_10") (pintype "input"))
      (node (ref "R38") (pin "1") (pinfunction "1_1") (pintype "passive"))
      (node (ref "R6") (pin "1") (pinfunction "1_1") (pintype "passive"))
    )
    (net (code "55") (name "Net-(IC1A-B)") (class "Default")
      (node (ref "IC1") (pin "9") (pinfunction "B_9") (pintype "input"))
      (node (ref "R39") (pin "1") (pinfunction "1_1") (pintype "passive"))
      (node (ref "R7") (pin "1") (pinfunction "1_1") (pintype "passive"))
    )
    (net (code "56") (name "Net-(L3-Pad1)") (class "Default")
      (node (ref "L3") (pin "1") (pinfunction "1_1") (pintype "passive"))
      (node (ref "L4") (pin "2") (pinfunction "2_2") (pintype "passive"))
    )
    (net (code "57") (name "Net-(L4-Pad1)") (class "Default")
      (node (ref "L4") (pin "1") (pinfunction "1_1") (pintype "passive"))
      (node (ref "R12") (pin "1") (pinfunction "1_1") (pintype "passive"))
      (node (ref "R32") (pin "2") (pinfunction "2_2") (pintype "passive"))
    )
    (net (code "58") (name "Net-(LED1-PadA)") (class "Default")
      (node (ref "LED1") (pin "A") (pinfunction "A_A") (pintype "passive"))
      (node (ref "R41") (pin "2") (pinfunction "2_2") (pintype "passive"))
    )
    (net (code "59") (name "Net-(LED2-PadA)") (class "Default")
      (node (ref "LED2") (pin "A") (pinfunction "A_A") (pintype "passive"))
      (node (ref "R60") (pin "2") (pinfunction "2_2") (pintype "passive"))
    )
    (net (code "60") (name "Net-(LED3-A)") (class "Default")
      (node (ref "LED3") (pin "A@1") (pinfunction "A_A@1") (pintype "passive"))
      (node (ref "R100") (pin "2") (pinfunction "2_2") (pintype "passive"))
    )
    (net (code "61") (name "Net-(LED4-PadA)") (class "Default")
      (node (ref "LED4") (pin "A") (pinfunction "A_A") (pintype "passive"))
      (node (ref "R23") (pin "2") (pinfunction "2_2") (pintype "passive"))
    )
    (net (code "62") (name "Net-(LED5-PadA)") (class "Default")
      (node (ref "LED5") (pin "A") (pinfunction "A_A") (pintype "passive"))
      (node (ref "R26") (pin "2") (pinfunction "2_2") (pintype "passive"))
    )
    (net (code "63") (name "Net-(LED6-A)") (class "Default")
      (node (ref "LED6") (pin "A@1") (pinfunction "A_A@1") (pintype "passive"))
      (node (ref "R12") (pin "2") (pinfunction "2_2") (pintype "passive"))
    )
    (net (code "64") (name "Net-(LED7-A)") (class "Default")
      (node (ref "LED7") (pin "A@1") (pinfunction "A_A@1") (pintype "passive"))
      (node (ref "R13") (pin "2") (pinfunction "2_2") (pintype "passive"))
    )
    (net (code "65") (name "Net-(Q2-B)") (class "Default")
      (node (ref "Q2") (pin "1") (pinfunction "B_1") (pintype "passive"))
      (node (ref "Q8") (pin "3") (pinfunction "C_3") (pintype "passive"))
    )
    (net (code "66") (name "Net-(Q2-C)") (class "Default")
      (node (ref "Q2") (pin "3") (pinfunction "C_3") (pintype "passive"))
      (node (ref "R2") (pin "1") (pinfunction "1_1") (pintype "passive"))
    )
    (net (code "67") (name "Net-(Q3-VIN)") (class "Default")
      (node (ref "C39") (pin "1") (pinfunction "1_1") (pintype "passive"))
      (node (ref "D13") (pin "C") (pinfunction "C_C") (pintype "passive"))
      (node (ref "D8") (pin "C") (pinfunction "C_C") (pintype "passive"))
      (node (ref "D9") (pin "C") (pinfunction "C_C") (pintype "passive"))
      (node (ref "Q3") (pin "3") (pinfunction "VIN_3") (pintype "power_in"))
    )
    (net (code "68") (name "Net-(Q4-C)") (class "Default")
      (node (ref "Q4") (pin "3") (pinfunction "C_3") (pintype "passive"))
      (node (ref "R27") (pin "1") (pinfunction "1_1") (pintype "passive"))
    )
    (net (code "69") (name "Net-(Q9-C)") (class "Default")
      (node (ref "Q9") (pin "3") (pinfunction "C_3") (pintype "passive"))
      (node (ref "R28") (pin "1") (pinfunction "1_1") (pintype "passive"))
    )
    (net (code "70") (name "Net-(Q10-C)") (class "Default")
      (node (ref "Q10") (pin "3") (pinfunction "C_3") (pintype "passive"))
      (node (ref "Q4") (pin "1") (pinfunction "B_1") (pintype "passive"))
    )
    (net (code "71") (name "Net-(Q12-C)") (class "Default")
      (node (ref "Q12") (pin "3") (pinfunction "C_3") (pintype "passive"))
      (node (ref "Q16") (pin "1") (pinfunction "B_1") (pintype "passive"))
    )
    (net (code "72") (name "Net-(Q13-C)") (class "Default")
      (node (ref "Q13") (pin "3") (pinfunction "C_3") (pintype "passive"))
      (node (ref "Q9") (pin "1") (pinfunction "B_1") (pintype "passive"))
    )
    (net (code "73") (name "Net-(Q14-B)") (class "Default")
      (node (ref "Q14") (pin "1") (pinfunction "B_1") (pintype "passive"))
      (node (ref "Q5") (pin "3") (pinfunction "C_3") (pintype "passive"))
    )
    (net (code "74") (name "Net-(Q14-C)") (class "Default")
      (node (ref "Q14") (pin "3") (pinfunction "C_3") (pintype "passive"))
      (node (ref "R25") (pin "1") (pinfunction "1_1") (pintype "passive"))
    )
    (net (code "75") (name "Net-(Q15-B)") (class "Default")
      (node (ref "Q15") (pin "1") (pinfunction "B_1") (pintype "passive"))
      (node (ref "Q6") (pin "3") (pinfunction "C_3") (pintype "passive"))
    )
    (net (code "76") (name "Net-(Q15-C)") (class "Default")
      (node (ref "Q15") (pin "3") (pinfunction "C_3") (pintype "passive"))
      (node (ref "R4") (pin "1") (pinfunction "1_1") (pintype "passive"))
    )
    (net (code "77") (name "Net-(Q16-C)") (class "Default")
      (node (ref "Q16") (pin "3") (pinfunction "C_3") (pintype "passive"))
      (node (ref "R32") (pin "1") (pinfunction "1_1") (pintype "passive"))
    )
    (net (code "78") (name "Net-(Q17-C)") (class "Default")
      (node (ref "Q17") (pin "3") (pinfunction "C_3") (pintype "passive"))
      (node (ref "Q18") (pin "1") (pinfunction "B_1") (pintype "passive"))
    )
    (net (code "79") (name "Net-(Q18-C)") (class "Default")
      (node (ref "Q18") (pin "3") (pinfunction "C_3") (pintype "passive"))
      (node (ref "R29") (pin "1") (pinfunction "1_1") (pintype "passive"))
    )
    (net (code "80") (name "Net-(Q19-C)") (class "Default")
      (node (ref "D1") (pin "A") (pinfunction "A_A") (pintype "passive"))
      (node (ref "Q19") (pin "3") (pinfunction "C_3") (pintype "passive"))
      (node (ref "R3") (pin "P$5") (pinfunction "-_P$5") (pintype "passive"))
    )
    (net (code "81") (name "Net-(Q20-C)") (class "Default")
      (node (ref "D2") (pin "A") (pinfunction "A_A") (pintype "passive"))
      (node (ref "Q20") (pin "3") (pinfunction "C_3") (pintype "passive"))
      (node (ref "R3") (pin "P$6") (pinfunction "-_P$6") (pintype "passive"))
    )
    (net (code "82") (name "Net-(R3D-5)") (class "Default")
      (node (ref "R3") (pin "P$3") (pinfunction "5_P$3") (pintype "passive"))
      (node (ref "TO_MKB_ANT_POS_1450_1475") (pin "1") (pinfunction "P_1") (pintype "passive"))
    )
    (net (code "83") (name "Net-(R13-Pad1)") (class "Default")
      (node (ref "R13") (pin "1") (pinfunction "1_1") (pintype "passive"))
      (node (ref "R22") (pin "1") (pinfunction "1_1") (pintype "passive"))
      (node (ref "R29") (pin "2") (pinfunction "2_2") (pintype "passive"))
    )
    (net (code "84") (name "Net-(R100-Pad1)") (class "Default")
      (node (ref "R100") (pin "1") (pinfunction "1_1") (pintype "passive"))
      (node (ref "R101") (pin "1") (pinfunction "1_1") (pintype "passive"))
      (node (ref "R28") (pin "2") (pinfunction "2_2") (pintype "passive"))
    )
    (net (code "85") (name "Net-(U$2-OSC1{slash}CLKI{slash}RA7)") (class "Default")
      (node (ref "C27") (pin "2") (pinfunction "2_2") (pintype "passive"))
      (node (ref "Q7") (pin "2") (pinfunction "2_2") (pintype "passive"))
      (node (ref "U$2") (pin "13") (pinfunction "OSC1/CLKI/RA7_13") (pintype "input"))
    )
    (net (code "86") (name "Net-(U$2-OSC2{slash}CLKO{slash}RA6)") (class "Default")
      (node (ref "C28") (pin "2") (pinfunction "2_2") (pintype "passive"))
      (node (ref "Q7") (pin "1") (pinfunction "1_1") (pintype "passive"))
      (node (ref "U$2") (pin "14") (pinfunction "OSC2/CLKO/RA6_14") (pintype "output"))
    )
    (net (code "87") (name "Net-(U$2-RD0{slash}PSP0)") (class "Default")
      (node (ref "R11") (pin "2") (pinfunction "2_2") (pintype "passive"))
      (node (ref "U$2") (pin "19") (pinfunction "RD0/PSP0_19") (pintype "bidirectional"))
    )
    (net (code "88") (name "Net-(VM3F-P$1)") (class "Default")
      (node (ref "R20") (pin "1") (pinfunction "1_1") (pintype "passive"))
      (node (ref "VM3") (pin "P$6") (pinfunction "P$1_P$6") (pintype "bidirectional"))
    )
    (net (code "89") (name "PIC_RX_HV") (class "Default")
      (node (ref "Q1") (pin "3") (pinfunction "D_3") (pintype "passive"))
      (node (ref "R17") (pin "2") (pinfunction "2_2") (pintype "passive"))
      (node (ref "U$2") (pin "26") (pinfunction "RC7/RX/DT_26") (pintype "bidirectional"))
    )
    (net (code "90") (name "PIC_TX_HV") (class "Default")
      (node (ref "Q11") (pin "3") (pinfunction "D_3") (pintype "passive"))
      (node (ref "R19") (pin "2") (pinfunction "2_2") (pintype "passive"))
      (node (ref "U$2") (pin "25") (pinfunction "RC6/TX/CK_25") (pintype "bidirectional"))
    )
    (net (code "91") (name "SCL") (class "Default")
      (node (ref "I2C_EXPA") (pin "P$2") (pinfunction "P$1_P$2") (pintype "bidirectional"))
      (node (ref "R67") (pin "1") (pinfunction "1_1") (pintype "passive"))
      (node (ref "U$2") (pin "18") (pinfunction "RC3/SCK/SCL_18") (pintype "bidirectional"))
    )
    (net (code "92") (name "SDA") (class "Default")
      (node (ref "I2C_EXPA") (pin "P$1") (pinfunction "P$1_P$1") (pintype "bidirectional"))
      (node (ref "R68") (pin "1") (pinfunction "1_1") (pintype "passive"))
      (node (ref "U$2") (pin "23") (pinfunction "RC4/SDI/SDA_23") (pintype "bidirectional"))
    )
    (net (code "93") (name "SWITCH_2_DAB_ANT") (class "Default")
      (node (ref "Q19") (pin "1") (pinfunction "B_1") (pintype "passive"))
      (node (ref "U$2") (pin "36") (pinfunction "RB3/AN9/CCP2_36") (pintype "bidirectional"))
    )
    (net (code "94") (name "SWITCH_2_FM_ANT") (class "Default")
      (node (ref "Q20") (pin "1") (pinfunction "B_1") (pintype "passive"))
      (node (ref "U$2") (pin "35") (pinfunction "RB2/INT2/AN8_35") (pintype "bidirectional"))
    )
    (net (code "95") (name "VM3_4.8V") (class "Default")
      (node (ref "C7") (pin "1") (pinfunction "1_1") (pintype "passive"))
      (node (ref "D9") (pin "A") (pinfunction "A_A") (pintype "passive"))
      (node (ref "R25") (pin "2") (pinfunction "2_2") (pintype "passive"))
      (node (ref "R60") (pin "1") (pinfunction "1_1") (pintype "passive"))
      (node (ref "VM3") (pin "P$3") (pinfunction "P$1_P$3") (pintype "bidirectional"))
    )
    (net (code "96") (name "VM3_PWR_ON_OFF") (class "Default")
      (node (ref "Q5") (pin "1") (pinfunction "B_1") (pintype "passive"))
      (node (ref "U$2") (pin "16") (pinfunction "RC1/T1OSI/CCP2_16") (pintype "bidirectional"))
    )
    (net (code "97") (name "VM3_RX") (class "Default")
      (node (ref "IC1") (pin "2") (pinfunction "Y2_2") (pintype "bidirectional"))
      (node (ref "VM3") (pin "P$4") (pinfunction "P$1_P$4") (pintype "bidirectional"))
    )
    (net (code "98") (name "VM3_TX") (class "Default")
      (node (ref "IC1") (pin "15") (pinfunction "X2_15") (pintype "bidirectional"))
      (node (ref "VM3") (pin "P$5") (pinfunction "P$1_P$5") (pintype "bidirectional"))
    )
    (net (code "99") (name "unconnected-(IC1A-X0-Pad12)") (class "Default")
      (node (ref "IC1") (pin "12") (pinfunction "X0_12") (pintype "bidirectional"))
    )
    (net (code "100") (name "unconnected-(IC1A-Y0-Pad1)") (class "Default")
      (node (ref "IC1") (pin "1") (pinfunction "Y0_1") (pintype "bidirectional"))
    )
    (net (code "101") (name "unconnected-(MKB_ICSP-Pad1)") (class "Default")
      (node (ref "MKB_ICSP") (pin "1") (pinfunction "1_1") (pintype "passive"))
    )
    (net (code "102") (name "unconnected-(MKB_ICSP-Pad5)") (class "Default")
      (node (ref "MKB_ICSP") (pin "5") (pinfunction "5_5") (pintype "passive"))
    )
    (net (code "103") (name "unconnected-(MKB_ICSP-Pad6)") (class "Default")
      (node (ref "MKB_ICSP") (pin "6") (pinfunction "6_6") (pintype "passive"))
    )
    (net (code "104") (name "unconnected-(MKB_UART-Pad3)") (class "Default")
      (node (ref "MKB_UART") (pin "3") (pinfunction "3_3") (pintype "passive"))
    )
    (net (code "105") (name "unconnected-(R14-Pad2)") (class "Default")
      (node (ref "R14") (pin "2") (pinfunction "2_2") (pintype "passive"))
    )
    (net (code "106") (name "unconnected-(R16-Pad2)") (class "Default")
      (node (ref "R16") (pin "2") (pinfunction "2_2") (pintype "passive"))
    )
    (net (code "107") (name "unconnected-(U$2-RB1{slash}INT1{slash}AN10-Pad34)") (class "Default")
      (node (ref "U$2") (pin "34") (pinfunction "RB1/INT1/AN10_34") (pintype "bidirectional"))
    )
    (net (code "108") (name "unconnected-(U$2-RD1{slash}PSP1-Pad20)") (class "Default")
      (node (ref "U$2") (pin "20") (pinfunction "RD1/PSP1_20") (pintype "bidirectional"))
    )
    (net (code "109") (name "unconnected-(U$2-RD4{slash}PSP4-Pad27)") (class "Default")
      (node (ref "U$2") (pin "27") (pinfunction "RD4/PSP4_27") (pintype "bidirectional"))
    )
    (net (code "110") (name "unconnected-(U$2-RD5{slash}PSP5{slash}P1B-Pad28)") (class "Default")
      (node (ref "U$2") (pin "28") (pinfunction "RD5/PSP5/P1B_28") (pintype "bidirectional"))
    )
    (net (code "111") (name "unconnected-(U$2-RD6{slash}PSP6{slash}P1C-Pad29)") (class "Default")
      (node (ref "U$2") (pin "29") (pinfunction "RD6/PSP6/P1C_29") (pintype "bidirectional"))
    )
  )
)
